# WIFI.net
KiCad netlist of a schematic drawn in Altium Designer
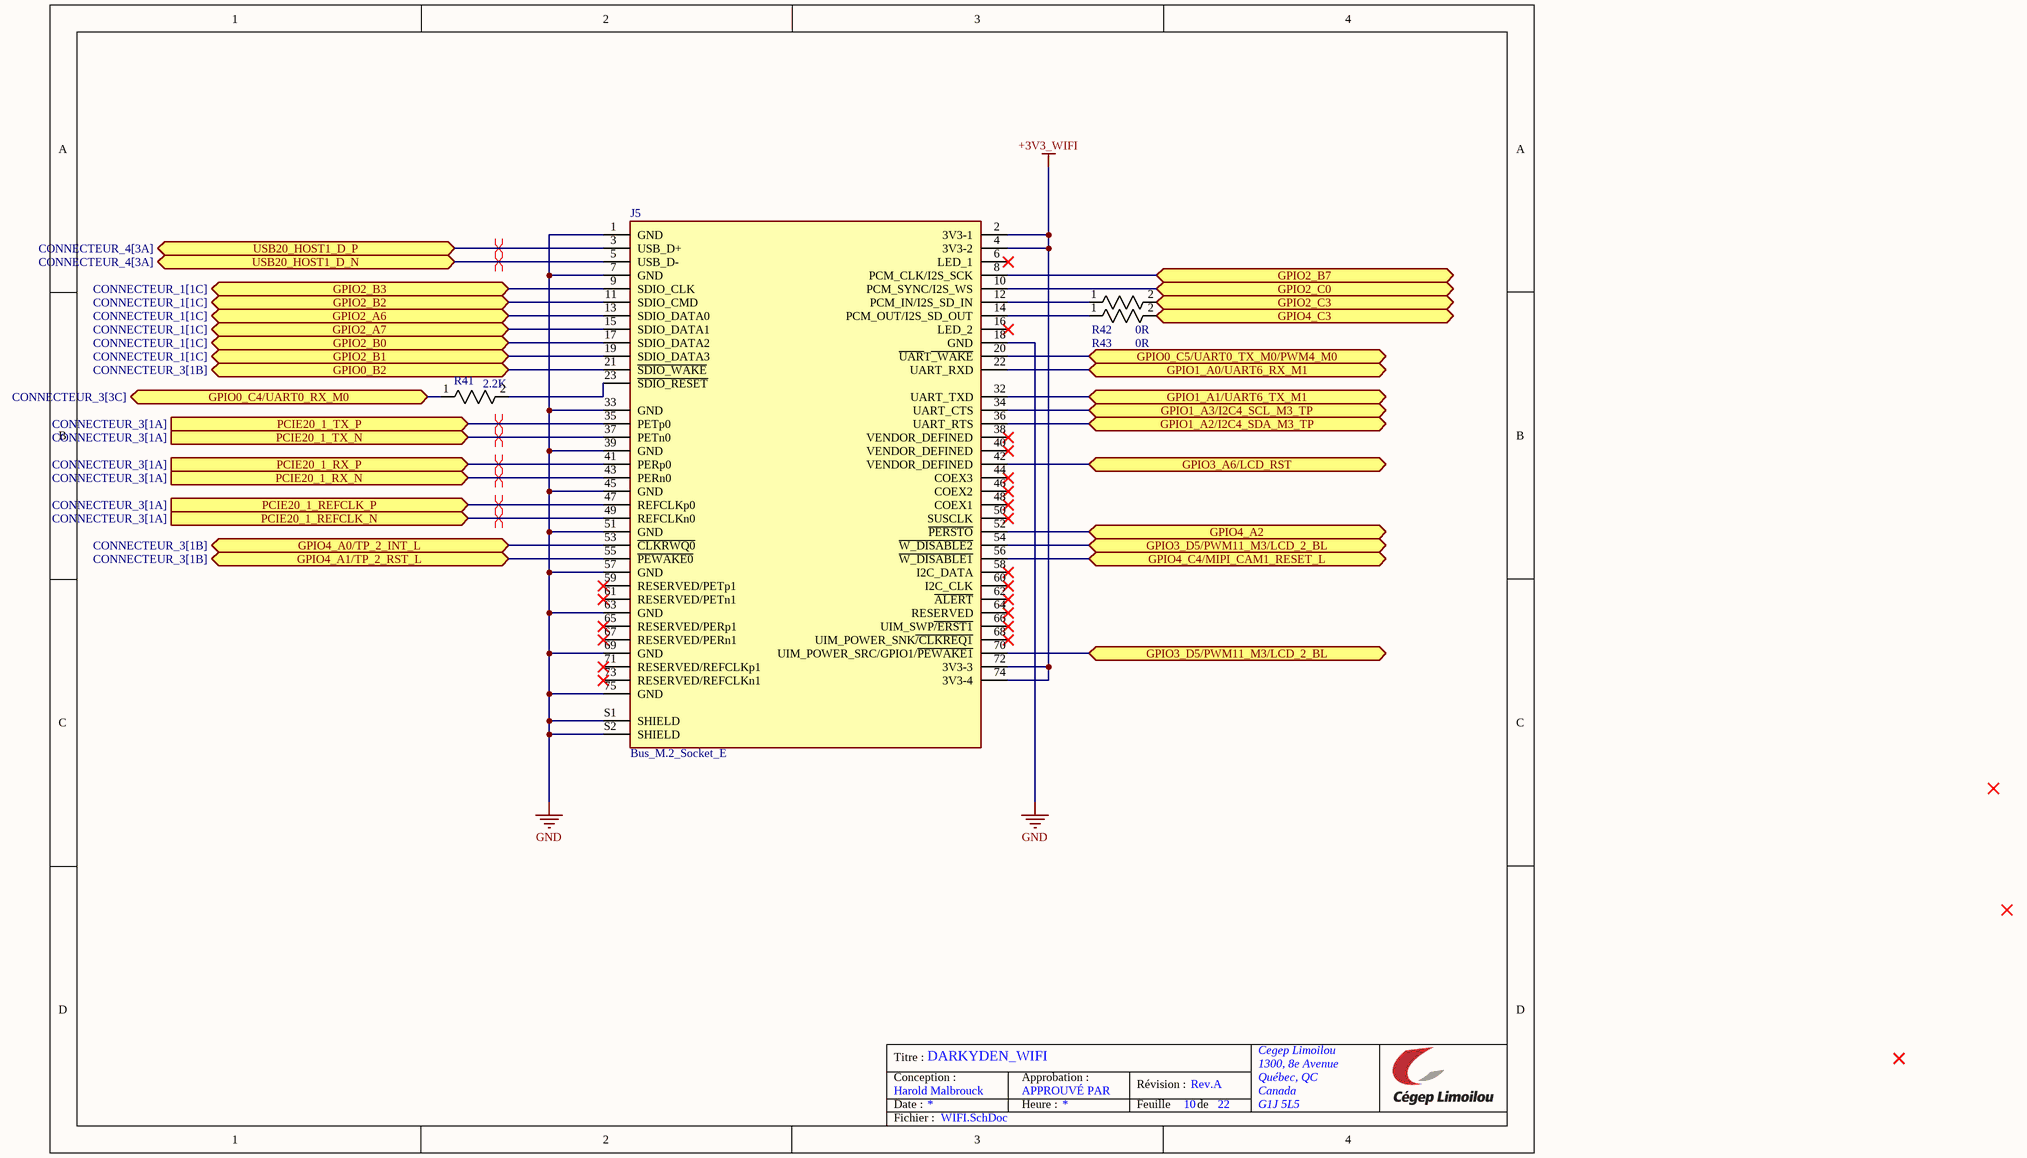
[diagram p0: WIFI.SchDoc]

(export (version "E")
  (design (tool "Eeschema 10.0.6"))
  (components
    (comp (ref "J5")
      (value "Bus_M.2_Socket_E")
      (footprint "AMPHENOL_MDT320E01001")
      (description "PCIe M.2 Connectors, Storage and Server Connector, P=0.5mm, H=3.2mm, Key E,30Î¼in Au Plating")
      (fields (field (name "MP") "MDT320E01001") (field (name "MF") "Amphenol ICC"))
      (libsource (lib "Bus_M.2_Socket_E") (part "Bus_M.2_Socket_E"))
    )
    (comp (ref "R41")
      (value "2.2K")
      (footprint "SamacSys:ERJ3EKF1000V")
      (description "2.2 kOhm, ï¿½ 5%, 100 mW, 0603 [1608 Metric], Thick Film, General Purpose")
      (fields
        (field (name "MANUFACTURER_PART_NUMBER") "ERJ-3GEYJ222V")
        (field (name "MOUSER PART NUMBER") "667-ERJ-3GEYJ222V")
      )
      (libsource (lib "SamacSys") (part "ERJ-3GEYJ222V"))
    )
    (comp (ref "R42")
      (value "0R")
      (footprint "SamacSys:ERJ3EKF1000V")
      (description "Zero Ohm Resistor, Jumper, 0603 [1608 Metric], Thick Film, 100 mW, 1 A, Surface Mount")
      (fields
        (field (name "MANUFACTURER_PART_NUMBER") "ERJ-3GEY0R00V")
        (field (name "MOUSER PART NUMBER") "667-ERJ-3GEY0R00V")
      )
      (libsource (lib "SamacSys") (part "ERJ-3GEY0R00V"))
    )
    (comp (ref "R43")
      (value "0R")
      (footprint "SamacSys:ERJ3EKF1000V")
      (description "Zero Ohm Resistor, Jumper, 0603 [1608 Metric], Thick Film, 100 mW, 1 A, Surface Mount")
      (fields
        (field (name "MANUFACTURER_PART_NUMBER") "ERJ-3GEY0R00V")
        (field (name "MOUSER PART NUMBER") "667-ERJ-3GEY0R00V")
      )
      (libsource (lib "SamacSys") (part "ERJ-3GEY0R00V"))
    )
  )
  (nets
    (net (code "1") (name "+3V3_WIFI") (class "Default")
      (node (ref "J5") (pin "2") (pinfunction "3V3-1_2") (pintype "power_in"))
      (node (ref "J5") (pin "4") (pinfunction "3V3-2_4") (pintype "power_in"))
      (node (ref "J5") (pin "72") (pinfunction "3V3-3_72") (pintype "power_in"))
      (node (ref "J5") (pin "74") (pinfunction "3V3-4_74") (pintype "power_in"))
    )
    (net (code "2") (name "/GPIO0_B2") (class "Default")
      (node (ref "J5") (pin "21") (pinfunction "~{SDIO_WAKE}_21") (pintype "passive"))
    )
    (net (code "3") (name "/GPIO0_C4{slash}UART0_RX_M0") (class "Default")
      (node (ref "R41") (pin "1") (pinfunction "1_1") (pintype "passive"))
    )
    (net (code "4") (name "/GPIO0_C5{slash}UART0_TX_M0{slash}PWM4_M0") (class "Default")
      (node (ref "J5") (pin "20") (pinfunction "~{UAR}T~{_WAKE}_20") (pintype "passive"))
    )
    (net (code "5") (name "/GPIO1_A0{slash}UART6_RX_M1") (class "Default")
      (node (ref "J5") (pin "22") (pinfunction "UART_RXD_22") (pintype "passive"))
    )
    (net (code "6") (name "/GPIO1_A1{slash}UART6_TX_M1") (class "Default")
      (node (ref "J5") (pin "32") (pinfunction "UART_TXD_32") (pintype "passive"))
    )
    (net (code "7") (name "/GPIO1_A2{slash}I2C4_SDA_M3_TP") (class "Default")
      (node (ref "J5") (pin "36") (pinfunction "UART_RTS_36") (pintype "passive"))
    )
    (net (code "8") (name "/GPIO1_A3{slash}I2C4_SCL_M3_TP") (class "Default")
      (node (ref "J5") (pin "34") (pinfunction "UART_CTS_34") (pintype "passive"))
    )
    (net (code "9") (name "/GPIO2_A6") (class "Default")
      (node (ref "J5") (pin "13") (pinfunction "SDIO_DATA0_13") (pintype "passive"))
    )
    (net (code "10") (name "/GPIO2_A7") (class "Default")
      (node (ref "J5") (pin "15") (pinfunction "SDIO_DATA1_15") (pintype "passive"))
    )
    (net (code "11") (name "/GPIO2_B0") (class "Default")
      (node (ref "J5") (pin "17") (pinfunction "SDIO_DATA2_17") (pintype "passive"))
    )
    (net (code "12") (name "/GPIO2_B1") (class "Default")
      (node (ref "J5") (pin "19") (pinfunction "SDIO_DATA3_19") (pintype "passive"))
    )
    (net (code "13") (name "/GPIO2_B2") (class "Default")
      (node (ref "J5") (pin "11") (pinfunction "SDIO_CMD_11") (pintype "passive"))
    )
    (net (code "14") (name "/GPIO2_B3") (class "Default")
      (node (ref "J5") (pin "9") (pinfunction "SDIO_CLK_9") (pintype "passive"))
    )
    (net (code "15") (name "/GPIO2_B7") (class "Default")
      (node (ref "J5") (pin "8") (pinfunction "PCM_CLK/I2S_SCK_8") (pintype "passive"))
    )
    (net (code "16") (name "/GPIO2_C0") (class "Default")
      (node (ref "J5") (pin "10") (pinfunction "PCM_SYNC/I2S_WS_10") (pintype "passive"))
    )
    (net (code "17") (name "/GPIO2_C3") (class "Default")
      (node (ref "R42") (pin "2") (pinfunction "2_2") (pintype "passive"))
    )
    (net (code "18") (name "/GPIO3_A6{slash}LCD_RST") (class "Default")
      (node (ref "J5") (pin "42") (pinfunction "VENDOR_DEFINED_42") (pintype "passive"))
    )
    (net (code "19") (name "/GPIO3_D5{slash}PWM11_M3{slash}LCD_2_BL") (class "Default")
      (node (ref "J5") (pin "54") (pinfunction "~{W_DISABLE2}_54") (pintype "passive"))
      (node (ref "J5") (pin "70") (pinfunction "UIM_POWER_SRC/GPIO1/~{PEWAKE1}_70") (pintype "passive"))
    )
    (net (code "20") (name "/GPIO4_A0{slash}TP_2_INT_L") (class "Default")
      (node (ref "J5") (pin "53") (pinfunction "~{CLKRWQ0}_53") (pintype "passive"))
    )
    (net (code "21") (name "/GPIO4_A1{slash}TP_2_RST_L") (class "Default")
      (node (ref "J5") (pin "55") (pinfunction "~{PEWAKE0}_55") (pintype "passive"))
    )
    (net (code "22") (name "/GPIO4_A2") (class "Default")
      (node (ref "J5") (pin "52") (pinfunction "~{PERSTO}_52") (pintype "passive"))
    )
    (net (code "23") (name "/GPIO4_C3") (class "Default")
      (node (ref "R43") (pin "2") (pinfunction "2_2") (pintype "passive"))
    )
    (net (code "24") (name "/GPIO4_C4{slash}MIPI_CAM1_RESET_L") (class "Default")
      (node (ref "J5") (pin "56") (pinfunction "~{W_DISABLE1}_56") (pintype "passive"))
    )
    (net (code "25") (name "/PCIE20_1_REFCLK_N") (class "Default")
      (node (ref "J5") (pin "49") (pinfunction "REFCLKn0_49") (pintype "passive"))
    )
    (net (code "26") (name "/PCIE20_1_REFCLK_P") (class "Default")
      (node (ref "J5") (pin "47") (pinfunction "REFCLKp0_47") (pintype "passive"))
    )
    (net (code "27") (name "/PCIE20_1_RX_N") (class "Default")
      (node (ref "J5") (pin "43") (pinfunction "PERn0_43") (pintype "passive"))
    )
    (net (code "28") (name "/PCIE20_1_RX_P") (class "Default")
      (node (ref "J5") (pin "41") (pinfunction "PERp0_41") (pintype "passive"))
    )
    (net (code "29") (name "/PCIE20_1_TX_N") (class "Default")
      (node (ref "J5") (pin "37") (pinfunction "PETn0_37") (pintype "passive"))
    )
    (net (code "30") (name "/PCIE20_1_TX_P") (class "Default")
      (node (ref "J5") (pin "35") (pinfunction "PETp0_35") (pintype "passive"))
    )
    (net (code "31") (name "/USB20_HOST1_D_N") (class "Default")
      (node (ref "J5") (pin "5") (pinfunction "USB_D-_5") (pintype "passive"))
    )
    (net (code "32") (name "/USB20_HOST1_D_P") (class "Default")
      (node (ref "J5") (pin "3") (pinfunction "USB_D+_3") (pintype "passive"))
    )
    (net (code "33") (name "GND") (class "Default")
      (node (ref "J5") (pin "1") (pinfunction "GND_1") (pintype "passive"))
      (node (ref "J5") (pin "18") (pinfunction "GND_18") (pintype "passive"))
      (node (ref "J5") (pin "33") (pinfunction "GND_33") (pintype "passive"))
      (node (ref "J5") (pin "39") (pinfunction "GND_39") (pintype "passive"))
      (node (ref "J5") (pin "45") (pinfunction "GND_45") (pintype "passive"))
      (node (ref "J5") (pin "51") (pinfunction "GND_51") (pintype "passive"))
      (node (ref "J5") (pin "57") (pinfunction "GND_57") (pintype "passive"))
      (node (ref "J5") (pin "63") (pinfunction "GND_63") (pintype "passive"))
      (node (ref "J5") (pin "69") (pinfunction "GND_69") (pintype "passive"))
      (node (ref "J5") (pin "7") (pinfunction "GND_7") (pintype "passive"))
      (node (ref "J5") (pin "75") (pinfunction "GND_75") (pintype "passive"))
      (node (ref "J5") (pin "S1") (pinfunction "SHIELD_S1") (pintype "passive"))
      (node (ref "J5") (pin "S2") (pinfunction "SHIELD_S2") (pintype "passive"))
    )
    (net (code "34") (name "Net-(J5-PCM_IN{slash}I2S_SD_IN)") (class "Default")
      (node (ref "J5") (pin "12") (pinfunction "PCM_IN/I2S_SD_IN_12") (pintype "passive"))
      (node (ref "R42") (pin "1") (pinfunction "1_1") (pintype "passive"))
    )
    (net (code "35") (name "Net-(J5-PCM_OUT{slash}I2S_SD_OUT)") (class "Default")
      (node (ref "J5") (pin "14") (pinfunction "PCM_OUT/I2S_SD_OUT_14") (pintype "passive"))
      (node (ref "R43") (pin "1") (pinfunction "1_1") (pintype "passive"))
    )
    (net (code "36") (name "Net-(J5-~{SDIO_RESET})") (class "Default")
      (node (ref "J5") (pin "23") (pinfunction "~{SDIO_RESET}_23") (pintype "passive"))
      (node (ref "R41") (pin "2") (pinfunction "2_2") (pintype "passive"))
    )
    (net (code "37") (name "unconnected-(J5-COEX1-Pad48)") (class "Default")
      (node (ref "J5") (pin "48") (pinfunction "COEX1_48") (pintype "passive+no_connect"))
    )
    (net (code "38") (name "unconnected-(J5-COEX2-Pad46)") (class "Default")
      (node (ref "J5") (pin "46") (pinfunction "COEX2_46") (pintype "passive+no_connect"))
    )
    (net (code "39") (name "unconnected-(J5-COEX3-Pad44)") (class "Default")
      (node (ref "J5") (pin "44") (pinfunction "COEX3_44") (pintype "passive+no_connect"))
    )
    (net (code "40") (name "unconnected-(J5-I2C_CLK-Pad60)") (class "Default")
      (node (ref "J5") (pin "60") (pinfunction "I2C_CLK_60") (pintype "passive+no_connect"))
    )
    (net (code "41") (name "unconnected-(J5-I2C_DATA-Pad58)") (class "Default")
      (node (ref "J5") (pin "58") (pinfunction "I2C_DATA_58") (pintype "passive+no_connect"))
    )
    (net (code "42") (name "unconnected-(J5-LED_1-Pad6)") (class "Default")
      (node (ref "J5") (pin "6") (pinfunction "LED_1_6") (pintype "passive+no_connect"))
    )
    (net (code "43") (name "unconnected-(J5-LED_2-Pad16)") (class "Default")
      (node (ref "J5") (pin "16") (pinfunction "LED_2_16") (pintype "passive+no_connect"))
    )
    (net (code "44") (name "unconnected-(J5-RESERVED-Pad64)") (class "Default")
      (node (ref "J5") (pin "64") (pinfunction "RESERVED_64") (pintype "passive+no_connect"))
    )
    (net (code "45") (name "unconnected-(J5-RESERVED{slash}PERn1-Pad67)") (class "Default")
      (node (ref "J5") (pin "67") (pinfunction "RESERVED/PERn1_67") (pintype "passive+no_connect"))
    )
    (net (code "46") (name "unconnected-(J5-RESERVED{slash}PERp1-Pad65)") (class "Default")
      (node (ref "J5") (pin "65") (pinfunction "RESERVED/PERp1_65") (pintype "passive+no_connect"))
    )
    (net (code "47") (name "unconnected-(J5-RESERVED{slash}PETn1-Pad61)") (class "Default")
      (node (ref "J5") (pin "61") (pinfunction "RESERVED/PETn1_61") (pintype "passive+no_connect"))
    )
    (net (code "48") (name "unconnected-(J5-RESERVED{slash}PETp1-Pad59)") (class "Default")
      (node (ref "J5") (pin "59") (pinfunction "RESERVED/PETp1_59") (pintype "passive+no_connect"))
    )
    (net (code "49") (name "unconnected-(J5-RESERVED{slash}REFCLKn1-Pad73)") (class "Default")
      (node (ref "J5") (pin "73") (pinfunction "RESERVED/REFCLKn1_73") (pintype "passive+no_connect"))
    )
    (net (code "50") (name "unconnected-(J5-RESERVED{slash}REFCLKp1-Pad71)") (class "Default")
      (node (ref "J5") (pin "71") (pinfunction "RESERVED/REFCLKp1_71") (pintype "passive+no_connect"))
    )
    (net (code "51") (name "unconnected-(J5-SUSCLK-Pad50)") (class "Default")
      (node (ref "J5") (pin "50") (pinfunction "SUSCLK_50") (pintype "passive+no_connect"))
    )
    (net (code "52") (name "unconnected-(J5-UIM_POWER_SNK~{{slash}CLKREQ1}-Pad68)") (class "Default")
      (node (ref "J5") (pin "68") (pinfunction "UIM_POWER_SNK~{/CLKREQ1}_68") (pintype "passive+no_connect"))
    )
    (net (code "53") (name "unconnected-(J5-UIM_SWP~{{slash}ERST1}-Pad66)") (class "Default")
      (node (ref "J5") (pin "66") (pinfunction "UIM_SWP~{/ERST1}_66") (pintype "passive+no_connect"))
    )
    (net (code "54") (name "unconnected-(J5-VENDOR_DEFINED-Pad38)") (class "Default")
      (node (ref "J5") (pin "38") (pinfunction "VENDOR_DEFINED_38") (pintype "passive+no_connect"))
    )
    (net (code "55") (name "unconnected-(J5-VENDOR_DEFINED-Pad40)") (class "Default")
      (node (ref "J5") (pin "40") (pinfunction "VENDOR_DEFINED_40") (pintype "passive+no_connect"))
    )
    (net (code "56") (name "unconnected-(J5-~{ALERT}-Pad62)") (class "Default")
      (node (ref "J5") (pin "62") (pinfunction "~{ALERT}_62") (pintype "passive+no_connect"))
    )
  )
)
